# hm-currentloop.net
KiCad netlist of a schematic drawn in EAGLE
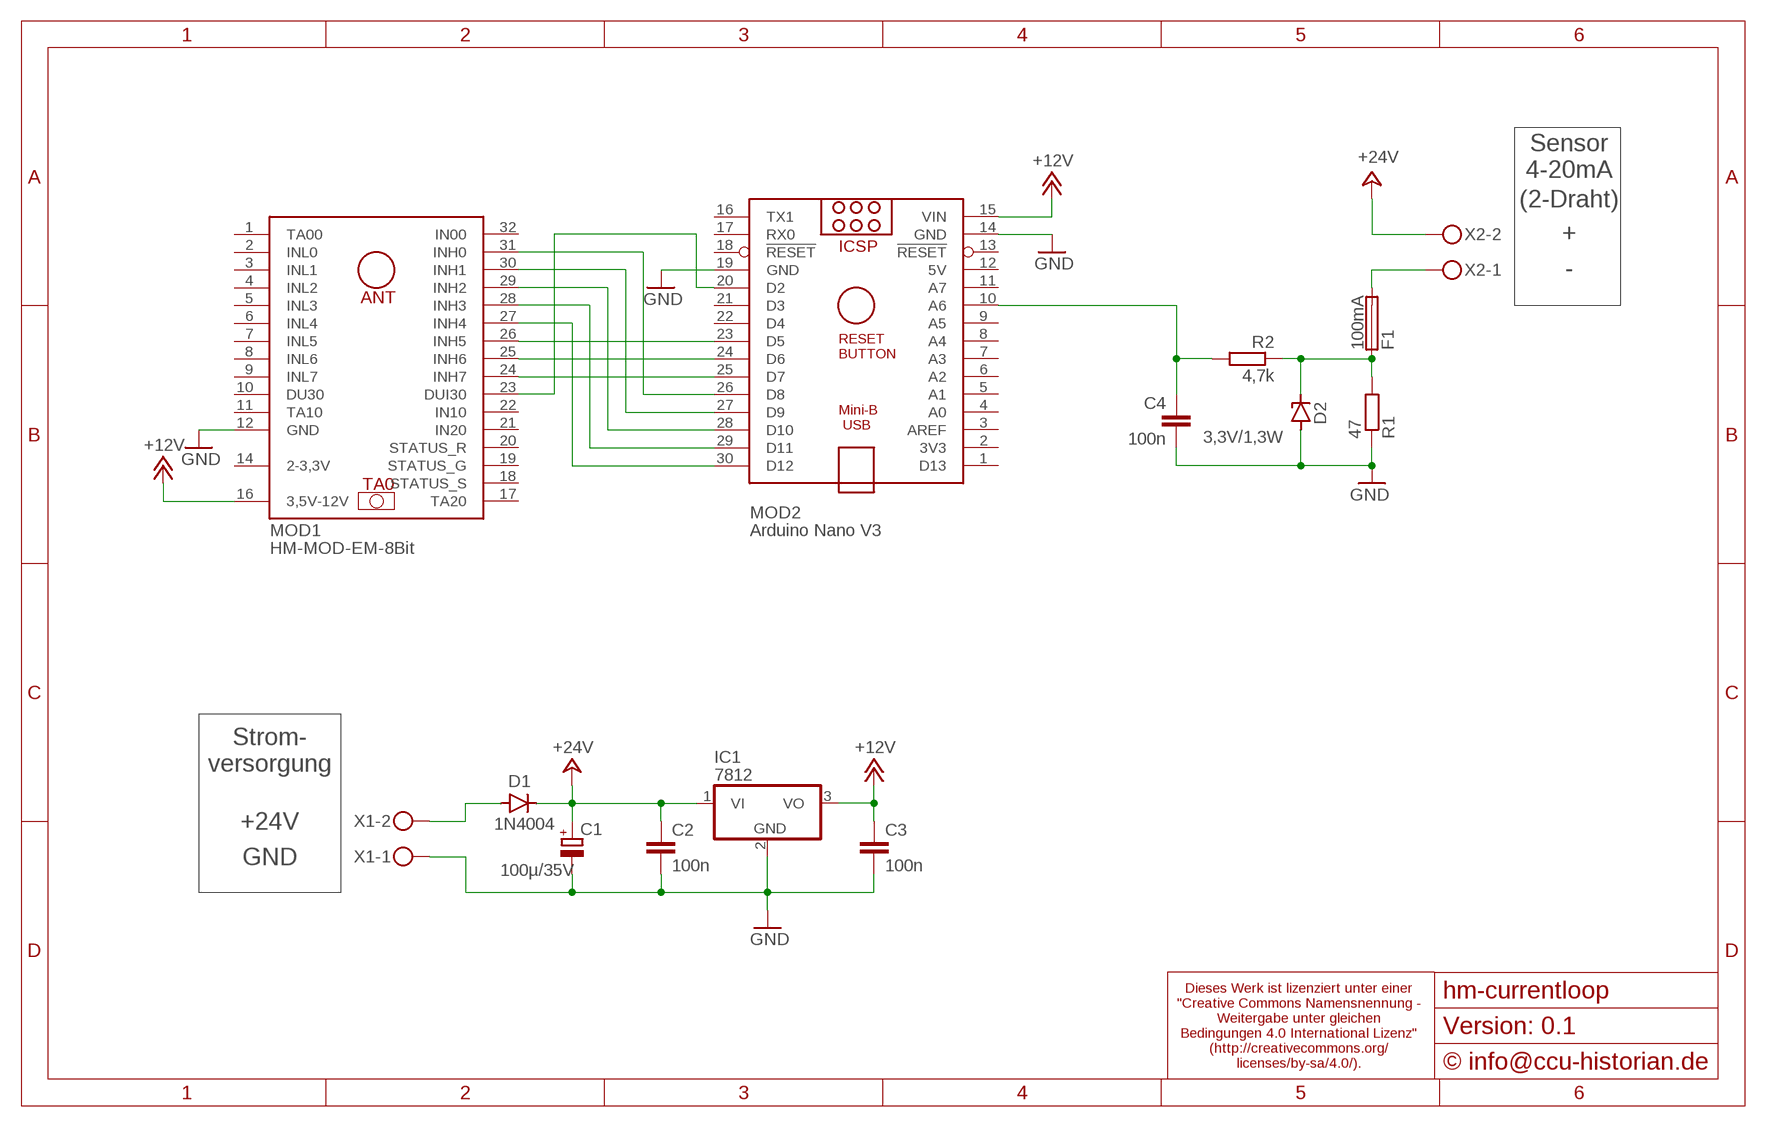
[diagram p0: schematic, sheet 1]

(export (version "E")
  (design (tool "Eeschema 10.0.6"))
  (components
    (comp (ref "C1")
      (value "100µ/35V")
      (footprint "eagle-import:E5-6")
      (libsource (lib "eagle-import") (part "CPOL-EUE5-6"))
    )
    (comp (ref "C2")
      (value "100n")
      (footprint "eagle-import:C050-025X075")
      (libsource (lib "eagle-import") (part "C-EU050-025X075"))
    )
    (comp (ref "C3")
      (value "100n")
      (footprint "eagle-import:C050-025X075")
      (libsource (lib "eagle-import") (part "C-EU050-025X075"))
    )
    (comp (ref "C4")
      (value "100n")
      (footprint "eagle-import:C050-025X075")
      (libsource (lib "eagle-import") (part "C-EU050-025X075"))
    )
    (comp (ref "D1")
      (value "1N4004")
      (footprint "eagle-import:DO41-10")
      (libsource (lib "eagle-import") (part "1N4004"))
    )
    (comp (ref "D2")
      (value "3,3V/1,3W")
      (footprint "eagle-import:F126Z10")
      (libsource (lib "eagle-import") (part "ZENER-DIODEF126-10"))
    )
    (comp (ref "F1")
      (value "100mA")
      (footprint "eagle-import:PICOFUSE")
      (libsource (lib "eagle-import") (part "PICOFUSE"))
    )
    (comp (ref "IC1")
      (value "7812")
      (footprint "eagle-import:TO220V")
      (libsource (lib "eagle-import") (part "78TV12"))
    )
    (comp (ref "MOD1")
      (value "HM-MOD-EM-8Bit")
      (footprint "eagle-import:HM-MOD")
      (libsource (lib "eagle-import") (part "HM-MOD-EM-8BIT"))
    )
    (comp (ref "MOD2")
      (value "Arduino Nano V3")
      (footprint "eagle-import:ARDUINO_NANO")
      (libsource (lib "eagle-import") (part "ARDUINO_NANO"))
    )
    (comp (ref "R1")
      (value "47")
      (footprint "eagle-import:0207_10")
      (libsource (lib "eagle-import") (part "R-EU_0207/10"))
    )
    (comp (ref "R2")
      (value "4,7k")
      (footprint "eagle-import:0207_10")
      (libsource (lib "eagle-import") (part "R-EU_0207/10"))
    )
    (comp (ref "X1")
      (value "MKDSN1,5/2-5,08")
      (footprint "eagle-import:MKDSN1,5_2-5,08")
      (libsource (lib "eagle-import") (part "MKDSN1,5/2-5,08"))
    )
    (comp (ref "X2")
      (value "MKDSN1,5/2-5,08")
      (footprint "eagle-import:MKDSN1,5_2-5,08")
      (libsource (lib "eagle-import") (part "MKDSN1,5/2-5,08"))
    )
  )
  (nets
    (net (code "1") (name "+12V") (class "Default")
      (node (ref "C3") (pin "1") (pinfunction "1_1") (pintype "passive"))
      (node (ref "IC1") (pin "3") (pinfunction "VO_3") (pintype "passive"))
      (node (ref "MOD1") (pin "16") (pinfunction "3,5V-12V_16") (pintype "power_in"))
      (node (ref "MOD2") (pin "15") (pinfunction "VIN_15") (pintype "power_in"))
    )
    (net (code "2") (name "+24V") (class "Default")
      (node (ref "C1") (pin "+") (pinfunction "+_+") (pintype "passive"))
      (node (ref "C2") (pin "1") (pinfunction "1_1") (pintype "passive"))
      (node (ref "D1") (pin "C") (pinfunction "C_C") (pintype "passive"))
      (node (ref "IC1") (pin "1") (pinfunction "VI_1") (pintype "input"))
      (node (ref "X2") (pin "2") (pinfunction "KL_2") (pintype "passive"))
    )
    (net (code "3") (name "/2-3,3V") (class "Default")
      (node (ref "MOD1") (pin "14") (pinfunction "2-3,3V_14") (pintype "power_in"))
    )
    (net (code "4") (name "/5V") (class "Default")
      (node (ref "MOD2") (pin "12") (pinfunction "5V_12") (pintype "power_in"))
    )
    (net (code "5") (name "GND") (class "Default")
      (node (ref "C1") (pin "-") (pinfunction "-_-") (pintype "passive"))
      (node (ref "C2") (pin "2") (pinfunction "2_2") (pintype "passive"))
      (node (ref "C3") (pin "2") (pinfunction "2_2") (pintype "passive"))
      (node (ref "C4") (pin "2") (pinfunction "2_2") (pintype "passive"))
      (node (ref "D2") (pin "A") (pinfunction "A_A") (pintype "passive"))
      (node (ref "IC1") (pin "2") (pinfunction "GND_2") (pintype "passive"))
      (node (ref "MOD1") (pin "12") (pinfunction "GND_12") (pintype "power_in"))
      (node (ref "MOD2") (pin "14") (pinfunction "GND_14") (pintype "power_in"))
      (node (ref "MOD2") (pin "19") (pinfunction "GND_19") (pintype "power_in"))
      (node (ref "R1") (pin "1") (pinfunction "1_1") (pintype "passive"))
      (node (ref "X1") (pin "1") (pinfunction "KL_1") (pintype "passive"))
    )
    (net (code "6") (name "Net-(D2-PadC)") (class "Default")
      (node (ref "D2") (pin "C") (pinfunction "C_C") (pintype "passive"))
      (node (ref "F1") (pin "1") (pinfunction "1_1") (pintype "passive"))
      (node (ref "R1") (pin "2") (pinfunction "2_2") (pintype "passive"))
      (node (ref "R2") (pin "1") (pinfunction "1_1") (pintype "passive"))
    )
    (net (code "7") (name "Net-(MOD1-DUI30)") (class "Default")
      (node (ref "MOD1") (pin "23") (pinfunction "DUI30_23") (pintype "input"))
      (node (ref "MOD2") (pin "20") (pinfunction "D2_20") (pintype "bidirectional"))
    )
    (net (code "8") (name "Net-(MOD1-INH0)") (class "Default")
      (node (ref "MOD1") (pin "31") (pinfunction "INH0_31") (pintype "input"))
      (node (ref "MOD2") (pin "26") (pinfunction "D8_26") (pintype "bidirectional"))
    )
    (net (code "9") (name "Net-(MOD1-INH1)") (class "Default")
      (node (ref "MOD1") (pin "30") (pinfunction "INH1_30") (pintype "input"))
      (node (ref "MOD2") (pin "27") (pinfunction "D9_27") (pintype "bidirectional"))
    )
    (net (code "10") (name "Net-(MOD1-INH2)") (class "Default")
      (node (ref "MOD1") (pin "29") (pinfunction "INH2_29") (pintype "input"))
      (node (ref "MOD2") (pin "28") (pinfunction "D10_28") (pintype "bidirectional"))
    )
    (net (code "11") (name "Net-(MOD1-INH3)") (class "Default")
      (node (ref "MOD1") (pin "28") (pinfunction "INH3_28") (pintype "input"))
      (node (ref "MOD2") (pin "29") (pinfunction "D11_29") (pintype "bidirectional"))
    )
    (net (code "12") (name "Net-(MOD1-INH4)") (class "Default")
      (node (ref "MOD1") (pin "27") (pinfunction "INH4_27") (pintype "input"))
      (node (ref "MOD2") (pin "30") (pinfunction "D12_30") (pintype "bidirectional"))
    )
    (net (code "13") (name "Net-(MOD1-INH5)") (class "Default")
      (node (ref "MOD1") (pin "26") (pinfunction "INH5_26") (pintype "input"))
      (node (ref "MOD2") (pin "23") (pinfunction "D5_23") (pintype "bidirectional"))
    )
    (net (code "14") (name "Net-(MOD1-INH6)") (class "Default")
      (node (ref "MOD1") (pin "25") (pinfunction "INH6_25") (pintype "input"))
      (node (ref "MOD2") (pin "24") (pinfunction "D6_24") (pintype "bidirectional"))
    )
    (net (code "15") (name "Net-(MOD1-INH7)") (class "Default")
      (node (ref "MOD1") (pin "24") (pinfunction "INH7_24") (pintype "input"))
      (node (ref "MOD2") (pin "25") (pinfunction "D7_25") (pintype "bidirectional"))
    )
    (net (code "16") (name "Net-(MOD2-A6)") (class "Default")
      (node (ref "C4") (pin "1") (pinfunction "1_1") (pintype "passive"))
      (node (ref "MOD2") (pin "10") (pinfunction "A6_10") (pintype "bidirectional"))
      (node (ref "R2") (pin "2") (pinfunction "2_2") (pintype "passive"))
    )
    (net (code "17") (name "Net-(X1B-KL)") (class "Default")
      (node (ref "D1") (pin "A") (pinfunction "A_A") (pintype "passive"))
      (node (ref "X1") (pin "2") (pinfunction "KL_2") (pintype "passive"))
    )
    (net (code "18") (name "Net-(X2A-KL)") (class "Default")
      (node (ref "F1") (pin "2") (pinfunction "2_2") (pintype "passive"))
      (node (ref "X2") (pin "1") (pinfunction "KL_1") (pintype "passive"))
    )
    (net (code "19") (name "unconnected-(MOD1-DU30-Pad10)") (class "Default")
      (node (ref "MOD1") (pin "10") (pinfunction "DU30_10") (pintype "input"))
    )
    (net (code "20") (name "unconnected-(MOD1-IN00-Pad32)") (class "Default")
      (node (ref "MOD1") (pin "32") (pinfunction "IN00_32") (pintype "input"))
    )
    (net (code "21") (name "unconnected-(MOD1-IN10-Pad22)") (class "Default")
      (node (ref "MOD1") (pin "22") (pinfunction "IN10_22") (pintype "input"))
    )
    (net (code "22") (name "unconnected-(MOD1-IN20-Pad21)") (class "Default")
      (node (ref "MOD1") (pin "21") (pinfunction "IN20_21") (pintype "input"))
    )
    (net (code "23") (name "unconnected-(MOD1-INL0-Pad2)") (class "Default")
      (node (ref "MOD1") (pin "2") (pinfunction "INL0_2") (pintype "input"))
    )
    (net (code "24") (name "unconnected-(MOD1-INL1-Pad3)") (class "Default")
      (node (ref "MOD1") (pin "3") (pinfunction "INL1_3") (pintype "input"))
    )
    (net (code "25") (name "unconnected-(MOD1-INL2-Pad4)") (class "Default")
      (node (ref "MOD1") (pin "4") (pinfunction "INL2_4") (pintype "input"))
    )
    (net (code "26") (name "unconnected-(MOD1-INL3-Pad5)") (class "Default")
      (node (ref "MOD1") (pin "5") (pinfunction "INL3_5") (pintype "input"))
    )
    (net (code "27") (name "unconnected-(MOD1-INL4-Pad6)") (class "Default")
      (node (ref "MOD1") (pin "6") (pinfunction "INL4_6") (pintype "input"))
    )
    (net (code "28") (name "unconnected-(MOD1-INL5-Pad7)") (class "Default")
      (node (ref "MOD1") (pin "7") (pinfunction "INL5_7") (pintype "input"))
    )
    (net (code "29") (name "unconnected-(MOD1-INL6-Pad8)") (class "Default")
      (node (ref "MOD1") (pin "8") (pinfunction "INL6_8") (pintype "input"))
    )
    (net (code "30") (name "unconnected-(MOD1-INL7-Pad9)") (class "Default")
      (node (ref "MOD1") (pin "9") (pinfunction "INL7_9") (pintype "input"))
    )
    (net (code "31") (name "unconnected-(MOD1-STATUS_G-Pad19)") (class "Default")
      (node (ref "MOD1") (pin "19") (pinfunction "STATUS_G_19") (pintype "output"))
    )
    (net (code "32") (name "unconnected-(MOD1-STATUS_R-Pad20)") (class "Default")
      (node (ref "MOD1") (pin "20") (pinfunction "STATUS_R_20") (pintype "output"))
    )
    (net (code "33") (name "unconnected-(MOD1-STATUS_S-Pad18)") (class "Default")
      (node (ref "MOD1") (pin "18") (pinfunction "STATUS_S_18") (pintype "output"))
    )
    (net (code "34") (name "unconnected-(MOD1-TA00-Pad1)") (class "Default")
      (node (ref "MOD1") (pin "1") (pinfunction "TA00_1") (pintype "input"))
    )
    (net (code "35") (name "unconnected-(MOD1-TA10-Pad11)") (class "Default")
      (node (ref "MOD1") (pin "11") (pinfunction "TA10_11") (pintype "input"))
    )
    (net (code "36") (name "unconnected-(MOD1-TA20-Pad17)") (class "Default")
      (node (ref "MOD1") (pin "17") (pinfunction "TA20_17") (pintype "input"))
    )
    (net (code "37") (name "unconnected-(MOD2-3V3-Pad2)") (class "Default")
      (node (ref "MOD2") (pin "2") (pinfunction "3V3_2") (pintype "output"))
    )
    (net (code "38") (name "unconnected-(MOD2-A0-Pad4)") (class "Default")
      (node (ref "MOD2") (pin "4") (pinfunction "A0_4") (pintype "bidirectional"))
    )
    (net (code "39") (name "unconnected-(MOD2-A1-Pad5)") (class "Default")
      (node (ref "MOD2") (pin "5") (pinfunction "A1_5") (pintype "bidirectional"))
    )
    (net (code "40") (name "unconnected-(MOD2-A2-Pad6)") (class "Default")
      (node (ref "MOD2") (pin "6") (pinfunction "A2_6") (pintype "bidirectional"))
    )
    (net (code "41") (name "unconnected-(MOD2-A3-Pad7)") (class "Default")
      (node (ref "MOD2") (pin "7") (pinfunction "A3_7") (pintype "bidirectional"))
    )
    (net (code "42") (name "unconnected-(MOD2-A4-Pad8)") (class "Default")
      (node (ref "MOD2") (pin "8") (pinfunction "A4_8") (pintype "bidirectional"))
    )
    (net (code "43") (name "unconnected-(MOD2-A5-Pad9)") (class "Default")
      (node (ref "MOD2") (pin "9") (pinfunction "A5_9") (pintype "bidirectional"))
    )
    (net (code "44") (name "unconnected-(MOD2-A7-Pad11)") (class "Default")
      (node (ref "MOD2") (pin "11") (pinfunction "A7_11") (pintype "bidirectional"))
    )
    (net (code "45") (name "unconnected-(MOD2-AREF-Pad3)") (class "Default")
      (node (ref "MOD2") (pin "3") (pinfunction "AREF_3") (pintype "input"))
    )
    (net (code "46") (name "unconnected-(MOD2-D3-Pad21)") (class "Default")
      (node (ref "MOD2") (pin "21") (pinfunction "D3_21") (pintype "bidirectional"))
    )
    (net (code "47") (name "unconnected-(MOD2-D4-Pad22)") (class "Default")
      (node (ref "MOD2") (pin "22") (pinfunction "D4_22") (pintype "bidirectional"))
    )
    (net (code "48") (name "unconnected-(MOD2-D13-Pad1)") (class "Default")
      (node (ref "MOD2") (pin "1") (pinfunction "D13_1") (pintype "bidirectional"))
    )
    (net (code "49") (name "unconnected-(MOD2-RX0-Pad17)") (class "Default")
      (node (ref "MOD2") (pin "17") (pinfunction "RX0_17") (pintype "bidirectional"))
    )
    (net (code "50") (name "unconnected-(MOD2-TX1-Pad16)") (class "Default")
      (node (ref "MOD2") (pin "16") (pinfunction "TX1_16") (pintype "bidirectional"))
    )
    (net (code "51") (name "unconnected-(MOD2-~{RESET}-Pad13)") (class "Default")
      (node (ref "MOD2") (pin "13") (pinfunction "~{RESET}_13") (pintype "input"))
    )
    (net (code "52") (name "unconnected-(MOD2-~{RESET}-Pad18)") (class "Default")
      (node (ref "MOD2") (pin "18") (pinfunction "~{RESET}_18") (pintype "input"))
    )
  )
)
